# SH8_-_CAN.net
KiCad netlist of a schematic drawn in Altium Designer
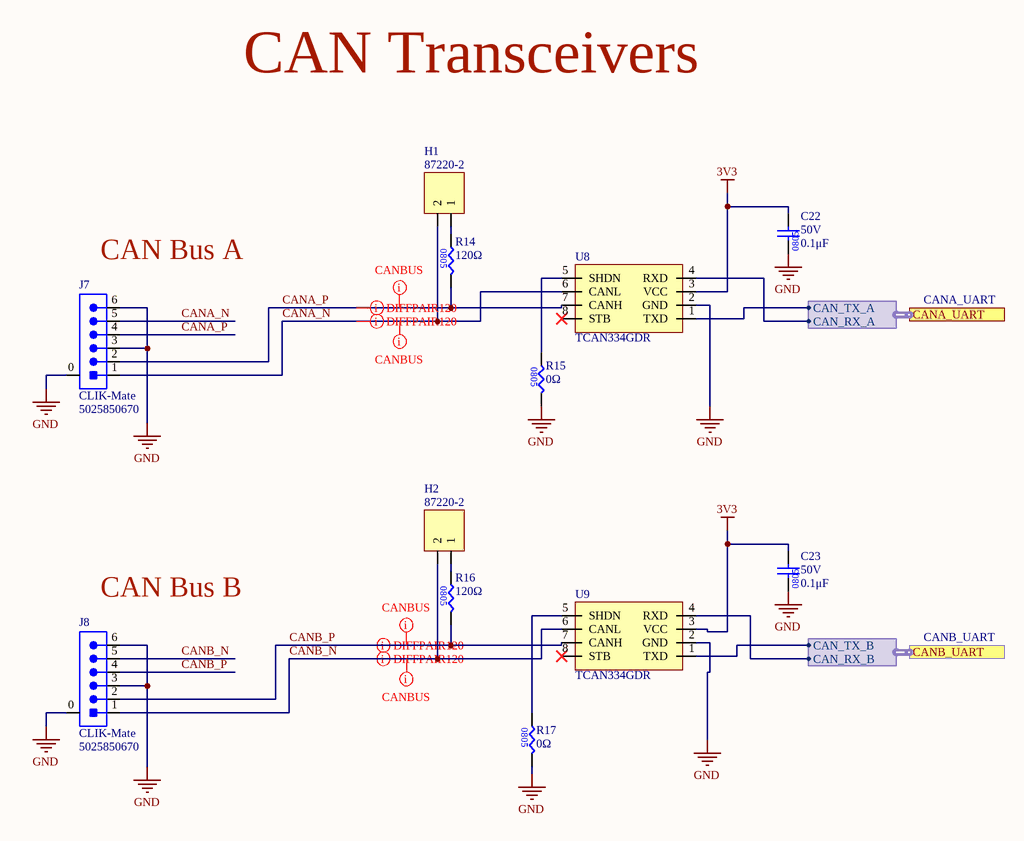
[diagram p0: SH8 - CAN.SchDoc]

(export (version "E")
  (design (tool "Eeschema 10.0.6"))
  (components
    (comp (ref "C22")
      (value "0.1μF")
      (footprint "CAP2012")
      (description "CAP CER 0.1UF 50V X7R 0805")
      (fields
        (field (name "VOLTAGE RATING") "50V")
        (field (name "LCSC PART #") "C49678")
        (field (name "Comment") "CAP_0.1uF_50V_0805")
      )
      (libsource (lib "UWRT_Schematic_Library_2020") (part "CAP_0.1uF_50V_0805"))
    )
    (comp (ref "C23")
      (value "0.1μF")
      (footprint "CAP2012")
      (description "CAP CER 0.1UF 50V X7R 0805")
      (fields
        (field (name "VOLTAGE RATING") "50V")
        (field (name "LCSC PART #") "C49678")
        (field (name "Comment") "CAP_0.1uF_50V_0805")
      )
      (libsource (lib "UWRT_Schematic_Library_2020") (part "CAP_0.1uF_50V_0805"))
    )
    (comp (ref "H1")
      (value "JUMPER_2")
      (footprint "HDR1X2")
      (description "HEADER 2X1")
      (fields (field (name "MANUFACTURER PART NUMBER 1") "87220-2"))
      (libsource (lib "UWRT_Schematic_Library_2020") (part "JUMPER_2"))
    )
    (comp (ref "H2")
      (value "JUMPER_2")
      (footprint "HDR1X2")
      (description "HEADER 2X1")
      (fields (field (name "MANUFACTURER PART NUMBER 1") "87220-2"))
      (libsource (lib "UWRT_Schematic_Library_2020") (part "JUMPER_2"))
    )
    (comp (ref "J7")
      (value "CON_6M_SM_RA_1.5mm")
      (footprint "MOLEX-5025850670")
      (description "CONN HEADER SMD RIGHT ANGLE 1.5 MM PITCH")
      (fields (field (name "FAMILY") "CLIK-Mate") (field (name "MANUFACTURER PART NUMBER 1") "5025850670"))
      (libsource (lib "UWRT_Schematic_Library_2020") (part "CON_6M_SM_RA_1.5mm"))
    )
    (comp (ref "J8")
      (value "CON_6M_SM_RA_1.5mm")
      (footprint "MOLEX-5025850670")
      (description "CONN HEADER SMD RIGHT ANGLE 1.5 MM PITCH")
      (fields (field (name "FAMILY") "CLIK-Mate") (field (name "MANUFACTURER PART NUMBER 1") "5025850670"))
      (libsource (lib "UWRT_Schematic_Library_2020") (part "CON_6M_SM_RA_1.5mm"))
    )
    (comp (ref "R14")
      (value "120Ω")
      (footprint "RES0805")
      (description "RES 120 OHM 1% 1/8W 0805")
      (fields (field (name "LCSC PART #") "C17437") (field (name "Comment") "RES_120Ω_0805_1%"))
      (libsource (lib "UWRT_Schematic_Library_2020") (part "RES_120Ω_0805_1%"))
    )
    (comp (ref "R15")
      (value "0Ω")
      (footprint "RES0805")
      (description "RES 0 OHM JUMPER 1/8W 0805")
      (fields (field (name "LCSC PART #") "C17477") (field (name "Comment") "RES_0Ω_0805"))
      (libsource (lib "UWRT_Schematic_Library_2020") (part "RES_0Ω_0805"))
    )
    (comp (ref "R16")
      (value "120Ω")
      (footprint "RES0805")
      (description "RES 120 OHM 1% 1/8W 0805")
      (fields (field (name "LCSC PART #") "C17437") (field (name "Comment") "RES_120Ω_0805_1%"))
      (libsource (lib "UWRT_Schematic_Library_2020") (part "RES_120Ω_0805_1%"))
    )
    (comp (ref "R17")
      (value "0Ω")
      (footprint "RES0805")
      (description "RES 0 OHM JUMPER 1/8W 0805")
      (fields (field (name "LCSC PART #") "C17477") (field (name "Comment") "RES_0Ω_0805"))
      (libsource (lib "UWRT_Schematic_Library_2020") (part "RES_0Ω_0805"))
    )
    (comp (ref "U8")
      (value "IC_CAN_TRANSCEIVER")
      (footprint "SOIC127P600X175-8N")
      (description "IC TRANSCEIVER 1/1 8SOIC")
      (fields (field (name "MANUFACTURER PART NUMBER 1") "TCAN334GDR"))
      (libsource (lib "UWRT_Schematic_Library_2020") (part "IC_CAN_TRANSCEIVER"))
    )
    (comp (ref "U9")
      (value "IC_CAN_TRANSCEIVER")
      (footprint "SOIC127P600X175-8N")
      (description "IC TRANSCEIVER 1/1 8SOIC")
      (fields (field (name "MANUFACTURER PART NUMBER 1") "TCAN334GDR"))
      (libsource (lib "UWRT_Schematic_Library_2020") (part "IC_CAN_TRANSCEIVER"))
    )
  )
  (nets
    (net (code "3") (name "/CANA_N") (class "Default")
      (node (ref "H1") (pin "2") (pinfunction "2_2") (pintype "passive"))
      (node (ref "J7") (pin "1") (pinfunction "1_1") (pintype "passive"))
      (node (ref "J7") (pin "5") (pinfunction "5_5") (pintype "passive"))
      (node (ref "U8") (pin "6") (pinfunction "CANL_6") (pintype "passive"))
    )
    (net (code "4") (name "/CANA_P") (class "Default")
      (node (ref "J7") (pin "2") (pinfunction "2_2") (pintype "passive"))
      (node (ref "J7") (pin "4") (pinfunction "4_4") (pintype "passive"))
      (node (ref "R14") (pin "2") (pinfunction "2_2") (pintype "passive"))
      (node (ref "U8") (pin "7") (pinfunction "CANH_7") (pintype "passive"))
    )
    (net (code "5") (name "/CANB_N") (class "Default")
      (node (ref "H2") (pin "2") (pinfunction "2_2") (pintype "passive"))
      (node (ref "J8") (pin "1") (pinfunction "1_1") (pintype "passive"))
      (node (ref "J8") (pin "5") (pinfunction "5_5") (pintype "passive"))
      (node (ref "U9") (pin "6") (pinfunction "CANL_6") (pintype "passive"))
    )
    (net (code "6") (name "/CANB_P") (class "Default")
      (node (ref "J8") (pin "2") (pinfunction "2_2") (pintype "passive"))
      (node (ref "J8") (pin "4") (pinfunction "4_4") (pintype "passive"))
      (node (ref "R16") (pin "2") (pinfunction "2_2") (pintype "passive"))
      (node (ref "U9") (pin "7") (pinfunction "CANH_7") (pintype "passive"))
    )
    (net (code "7") (name "/CAN_RX_A") (class "Default")
      (node (ref "U8") (pin "4") (pinfunction "RXD_4") (pintype "passive"))
    )
    (net (code "8") (name "/CAN_RX_B") (class "Default")
      (node (ref "U9") (pin "4") (pinfunction "RXD_4") (pintype "passive"))
    )
    (net (code "9") (name "/CAN_TX_A") (class "Default")
      (node (ref "U8") (pin "1") (pinfunction "TXD_1") (pintype "passive"))
    )
    (net (code "10") (name "/CAN_TX_B") (class "Default")
      (node (ref "U9") (pin "1") (pinfunction "TXD_1") (pintype "passive"))
    )
    (net (code "13") (name "3V3") (class "Default")
      (node (ref "C22") (pin "2") (pinfunction "2_2") (pintype "passive"))
      (node (ref "C23") (pin "2") (pinfunction "2_2") (pintype "passive"))
      (node (ref "U8") (pin "3") (pinfunction "VCC_3") (pintype "passive"))
      (node (ref "U9") (pin "3") (pinfunction "VCC_3") (pintype "passive"))
    )
    (net (code "14") (name "GND") (class "Default")
      (node (ref "C22") (pin "1") (pinfunction "1_1") (pintype "passive"))
      (node (ref "C23") (pin "1") (pinfunction "1_1") (pintype "passive"))
      (node (ref "J7") (pin "0") (pinfunction "0_0") (pintype "passive"))
      (node (ref "J7") (pin "3") (pinfunction "3_3") (pintype "passive"))
      (node (ref "J7") (pin "6") (pinfunction "6_6") (pintype "passive"))
      (node (ref "J8") (pin "0") (pinfunction "0_0") (pintype "passive"))
      (node (ref "J8") (pin "3") (pinfunction "3_3") (pintype "passive"))
      (node (ref "J8") (pin "6") (pinfunction "6_6") (pintype "passive"))
      (node (ref "R15") (pin "2") (pinfunction "2_2") (pintype "passive"))
      (node (ref "R17") (pin "2") (pinfunction "2_2") (pintype "passive"))
      (node (ref "U8") (pin "2") (pinfunction "GND_2") (pintype "passive"))
      (node (ref "U9") (pin "2") (pinfunction "GND_2") (pintype "passive"))
    )
    (net (code "15") (name "Net-(H1-Pad1)") (class "Default")
      (node (ref "H1") (pin "1") (pinfunction "1_1") (pintype "passive"))
      (node (ref "R14") (pin "1") (pinfunction "1_1") (pintype "passive"))
    )
    (net (code "16") (name "Net-(H2-Pad1)") (class "Default")
      (node (ref "H2") (pin "1") (pinfunction "1_1") (pintype "passive"))
      (node (ref "R16") (pin "1") (pinfunction "1_1") (pintype "passive"))
    )
    (net (code "17") (name "Net-(U8-SHDN)") (class "Default")
      (node (ref "R15") (pin "1") (pinfunction "1_1") (pintype "passive"))
      (node (ref "U8") (pin "5") (pinfunction "SHDN_5") (pintype "passive"))
    )
    (net (code "18") (name "Net-(U9-SHDN)") (class "Default")
      (node (ref "R17") (pin "1") (pinfunction "1_1") (pintype "passive"))
      (node (ref "U9") (pin "5") (pinfunction "SHDN_5") (pintype "passive"))
    )
    (net (code "19") (name "unconnected-(U8-STB-Pad8)") (class "Default")
      (node (ref "U8") (pin "8") (pinfunction "STB_8") (pintype "passive+no_connect"))
    )
    (net (code "20") (name "unconnected-(U9-STB-Pad8)") (class "Default")
      (node (ref "U9") (pin "8") (pinfunction "STB_8") (pintype "passive+no_connect"))
    )
  )
)
